# synthbadge.net
KiCad netlist of a schematic drawn in EAGLE
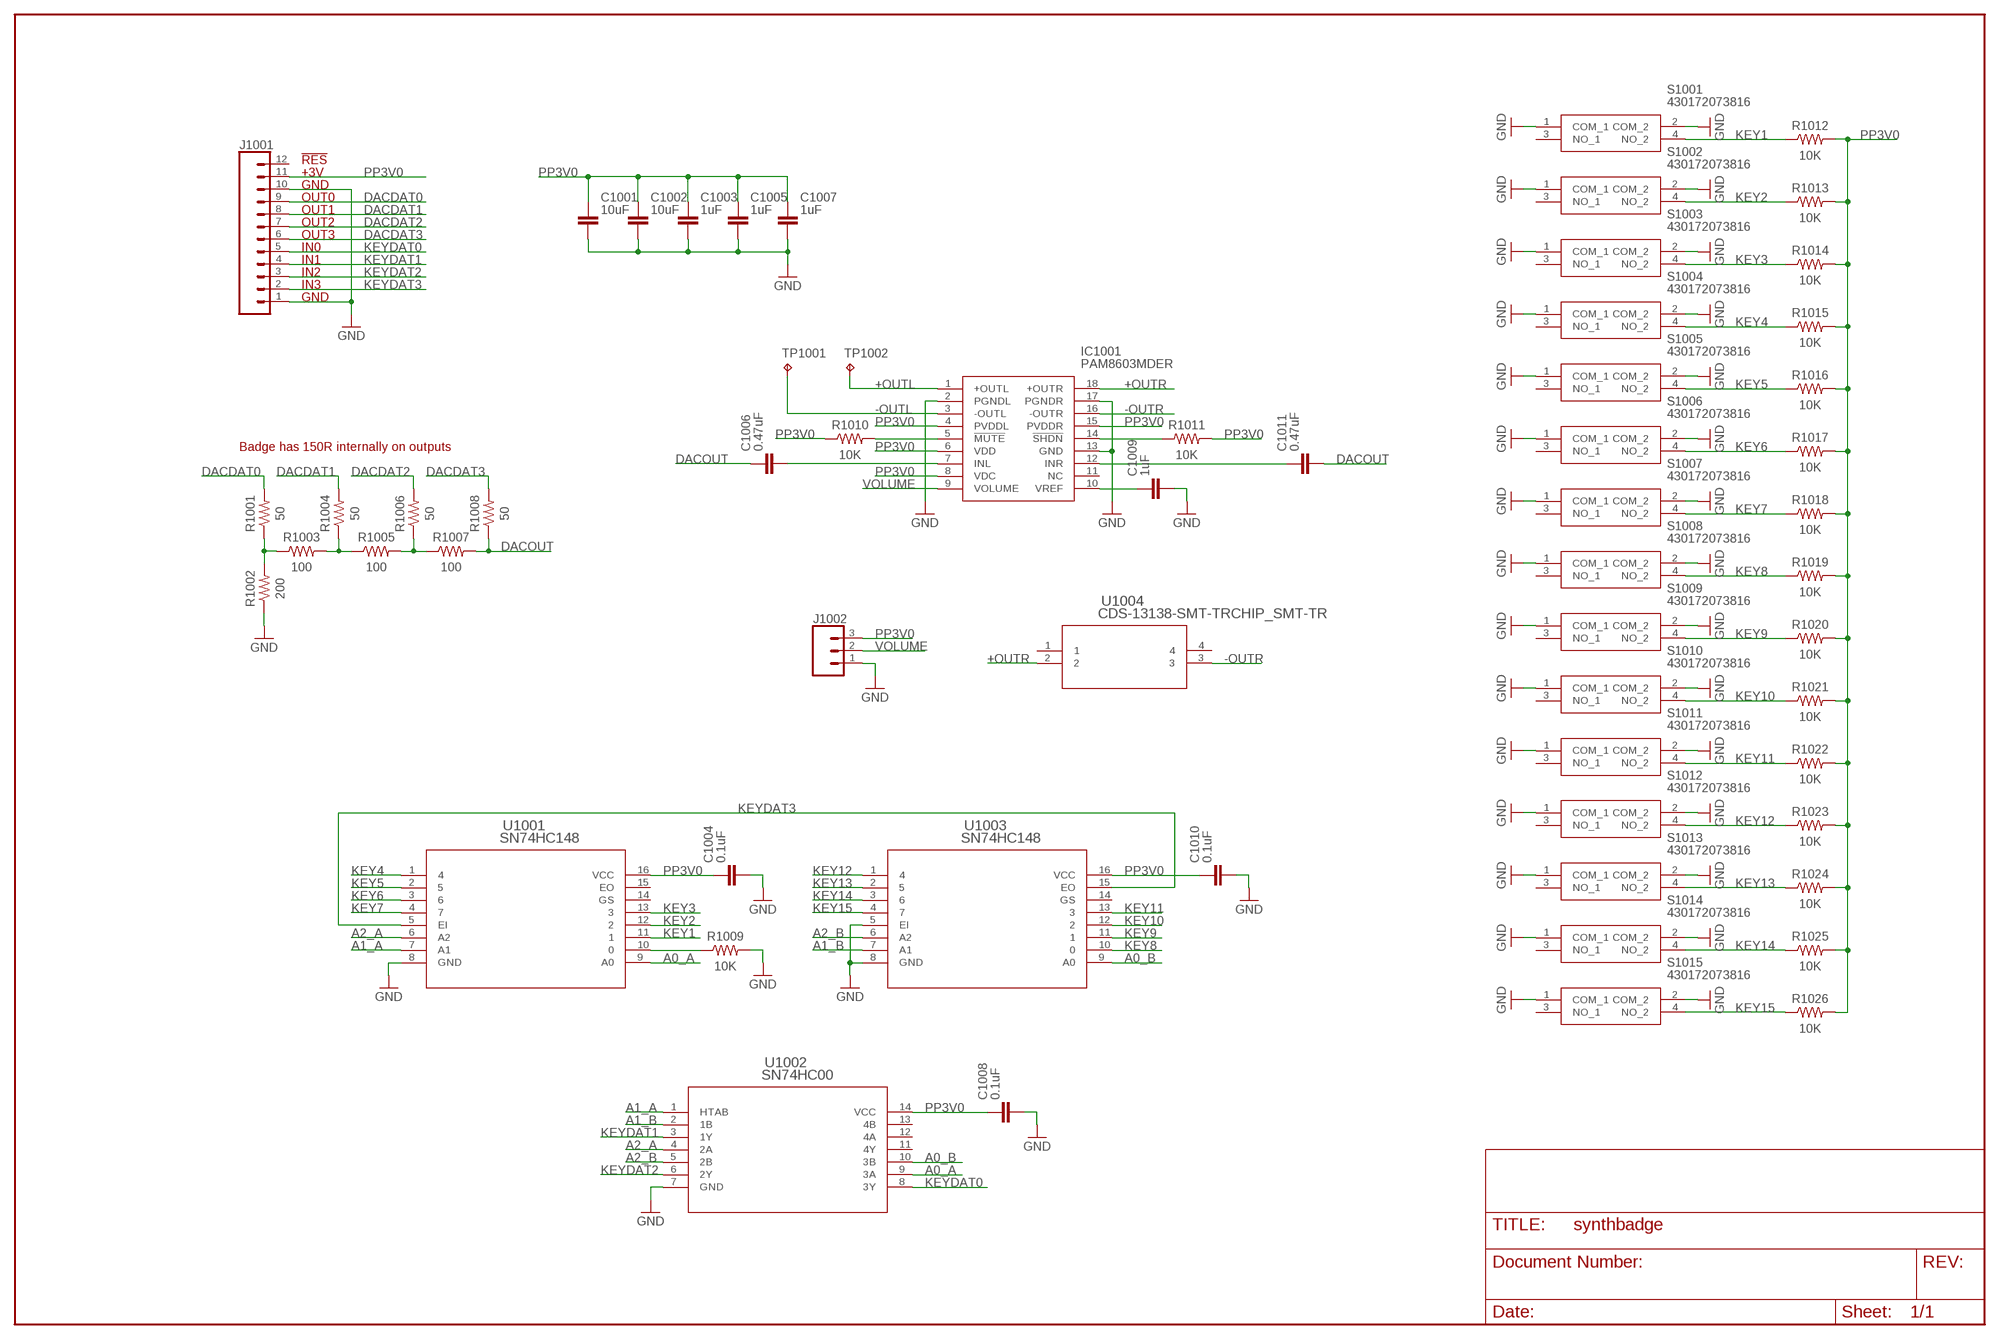
[diagram p0: schematic, sheet 1]

(export (version "E")
  (design (tool "Eeschema 10.0.6"))
  (components
    (comp (ref "C1001")
      (value "10uF")
      (footprint "eagle-import:CAPC2012X110")
      (libsource (lib "eagle-import") (part "CCHIP-0805(2012-METRIC)_"))
    )
    (comp (ref "C1002")
      (value "10uF")
      (footprint "eagle-import:CAPC2012X110")
      (libsource (lib "eagle-import") (part "CCHIP-0805(2012-METRIC)_"))
    )
    (comp (ref "C1003")
      (value "1uF")
      (footprint "eagle-import:CAPC2012X110")
      (libsource (lib "eagle-import") (part "CCHIP-0805(2012-METRIC)_"))
    )
    (comp (ref "C1004")
      (value "0.1uF")
      (footprint "eagle-import:CAPC2012X110")
      (libsource (lib "eagle-import") (part "CCHIP-0805(2012-METRIC)_"))
    )
    (comp (ref "C1005")
      (value "1uF")
      (footprint "eagle-import:CAPC2012X110")
      (libsource (lib "eagle-import") (part "CCHIP-0805(2012-METRIC)_"))
    )
    (comp (ref "C1006")
      (value "0.47uF")
      (footprint "eagle-import:CAPC2012X110")
      (libsource (lib "eagle-import") (part "CCHIP-0805(2012-METRIC)_"))
    )
    (comp (ref "C1007")
      (value "1uF")
      (footprint "eagle-import:CAPC2012X110")
      (libsource (lib "eagle-import") (part "CCHIP-0805(2012-METRIC)_"))
    )
    (comp (ref "C1008")
      (value "0.1uF")
      (footprint "eagle-import:CAPC2012X110")
      (libsource (lib "eagle-import") (part "CCHIP-0805(2012-METRIC)_"))
    )
    (comp (ref "C1009")
      (value "1uF")
      (footprint "eagle-import:CAPC2012X110")
      (libsource (lib "eagle-import") (part "CCHIP-0805(2012-METRIC)_"))
    )
    (comp (ref "C1010")
      (value "0.1uF")
      (footprint "eagle-import:CAPC2012X110")
      (libsource (lib "eagle-import") (part "CCHIP-0805(2012-METRIC)_"))
    )
    (comp (ref "C1011")
      (value "0.47uF")
      (footprint "eagle-import:CAPC2012X110")
      (libsource (lib "eagle-import") (part "CCHIP-0805(2012-METRIC)_"))
    )
    (comp (ref "IC1001")
      (value "PAM8603MDER")
      (footprint "eagle-import:SOIC127P1032X270-18N")
      (fields (field (name "MOUSER_PART_NUMBER") "621-PAM8603MDER"))
      (libsource (lib "eagle-import") (part "PAM8603MDER"))
    )
    (comp (ref "J1001")
      (value "CONN_12")
      (footprint "eagle-import:1X12")
      (libsource (lib "eagle-import") (part "CONN_12"))
    )
    (comp (ref "J1002")
      (value "CONN_03")
      (footprint "eagle-import:1X03")
      (libsource (lib "eagle-import") (part "CONN_03"))
    )
    (comp (ref "R1001")
      (value "50")
      (footprint "eagle-import:RESC2012X65")
      (libsource (lib "eagle-import") (part "R-USCHIP-0805(2012-METRIC)_"))
    )
    (comp (ref "R1002")
      (value "200")
      (footprint "eagle-import:RESC2012X65")
      (libsource (lib "eagle-import") (part "R-USCHIP-0805(2012-METRIC)_"))
    )
    (comp (ref "R1003")
      (value "100")
      (footprint "eagle-import:RESC2012X65")
      (libsource (lib "eagle-import") (part "R-USCHIP-0805(2012-METRIC)_"))
    )
    (comp (ref "R1004")
      (value "50")
      (footprint "eagle-import:RESC2012X65")
      (libsource (lib "eagle-import") (part "R-USCHIP-0805(2012-METRIC)_"))
    )
    (comp (ref "R1005")
      (value "100")
      (footprint "eagle-import:RESC2012X65")
      (libsource (lib "eagle-import") (part "R-USCHIP-0805(2012-METRIC)_"))
    )
    (comp (ref "R1006")
      (value "50")
      (footprint "eagle-import:RESC2012X65")
      (libsource (lib "eagle-import") (part "R-USCHIP-0805(2012-METRIC)_"))
    )
    (comp (ref "R1007")
      (value "100")
      (footprint "eagle-import:RESC2012X65")
      (libsource (lib "eagle-import") (part "R-USCHIP-0805(2012-METRIC)_"))
    )
    (comp (ref "R1008")
      (value "50")
      (footprint "eagle-import:RESC2012X65")
      (libsource (lib "eagle-import") (part "R-USCHIP-0805(2012-METRIC)_"))
    )
    (comp (ref "R1009")
      (value "10K")
      (footprint "eagle-import:RESC2012X65")
      (libsource (lib "eagle-import") (part "R-USCHIP-0805(2012-METRIC)_"))
    )
    (comp (ref "R1010")
      (value "10K")
      (footprint "eagle-import:RESC2012X65")
      (libsource (lib "eagle-import") (part "R-USCHIP-0805(2012-METRIC)_"))
    )
    (comp (ref "R1011")
      (value "10K")
      (footprint "eagle-import:RESC2012X65")
      (libsource (lib "eagle-import") (part "R-USCHIP-0805(2012-METRIC)_"))
    )
    (comp (ref "R1012")
      (value "10K")
      (footprint "eagle-import:RESC2012X65")
      (libsource (lib "eagle-import") (part "R-USCHIP-0805(2012-METRIC)_"))
    )
    (comp (ref "R1013")
      (value "10K")
      (footprint "eagle-import:RESC2012X65")
      (libsource (lib "eagle-import") (part "R-USCHIP-0805(2012-METRIC)_"))
    )
    (comp (ref "R1014")
      (value "10K")
      (footprint "eagle-import:RESC2012X65")
      (libsource (lib "eagle-import") (part "R-USCHIP-0805(2012-METRIC)_"))
    )
    (comp (ref "R1015")
      (value "10K")
      (footprint "eagle-import:RESC2012X65")
      (libsource (lib "eagle-import") (part "R-USCHIP-0805(2012-METRIC)_"))
    )
    (comp (ref "R1016")
      (value "10K")
      (footprint "eagle-import:RESC2012X65")
      (libsource (lib "eagle-import") (part "R-USCHIP-0805(2012-METRIC)_"))
    )
    (comp (ref "R1017")
      (value "10K")
      (footprint "eagle-import:RESC2012X65")
      (libsource (lib "eagle-import") (part "R-USCHIP-0805(2012-METRIC)_"))
    )
    (comp (ref "R1018")
      (value "10K")
      (footprint "eagle-import:RESC2012X65")
      (libsource (lib "eagle-import") (part "R-USCHIP-0805(2012-METRIC)_"))
    )
    (comp (ref "R1019")
      (value "10K")
      (footprint "eagle-import:RESC2012X65")
      (libsource (lib "eagle-import") (part "R-USCHIP-0805(2012-METRIC)_"))
    )
    (comp (ref "R1020")
      (value "10K")
      (footprint "eagle-import:RESC2012X65")
      (libsource (lib "eagle-import") (part "R-USCHIP-0805(2012-METRIC)_"))
    )
    (comp (ref "R1021")
      (value "10K")
      (footprint "eagle-import:RESC2012X65")
      (libsource (lib "eagle-import") (part "R-USCHIP-0805(2012-METRIC)_"))
    )
    (comp (ref "R1022")
      (value "10K")
      (footprint "eagle-import:RESC2012X65")
      (libsource (lib "eagle-import") (part "R-USCHIP-0805(2012-METRIC)_"))
    )
    (comp (ref "R1023")
      (value "10K")
      (footprint "eagle-import:RESC2012X65")
      (libsource (lib "eagle-import") (part "R-USCHIP-0805(2012-METRIC)_"))
    )
    (comp (ref "R1024")
      (value "10K")
      (footprint "eagle-import:RESC2012X65")
      (libsource (lib "eagle-import") (part "R-USCHIP-0805(2012-METRIC)_"))
    )
    (comp (ref "R1025")
      (value "10K")
      (footprint "eagle-import:RESC2012X65")
      (libsource (lib "eagle-import") (part "R-USCHIP-0805(2012-METRIC)_"))
    )
    (comp (ref "R1026")
      (value "10K")
      (footprint "eagle-import:RESC2012X65")
      (libsource (lib "eagle-import") (part "R-USCHIP-0805(2012-METRIC)_"))
    )
    (comp (ref "S1001")
      (value "430172073816")
      (footprint "eagle-import:430172073816")
      (fields (field (name "MOUSER_PART_NUMBER") "710-430172073816"))
      (libsource (lib "eagle-import") (part "430172073816"))
    )
    (comp (ref "S1002")
      (value "430172073816")
      (footprint "eagle-import:430172073816")
      (fields (field (name "MOUSER_PART_NUMBER") "710-430172073816"))
      (libsource (lib "eagle-import") (part "430172073816"))
    )
    (comp (ref "S1003")
      (value "430172073816")
      (footprint "eagle-import:430172073816")
      (fields (field (name "MOUSER_PART_NUMBER") "710-430172073816"))
      (libsource (lib "eagle-import") (part "430172073816"))
    )
    (comp (ref "S1004")
      (value "430172073816")
      (footprint "eagle-import:430172073816")
      (fields (field (name "MOUSER_PART_NUMBER") "710-430172073816"))
      (libsource (lib "eagle-import") (part "430172073816"))
    )
    (comp (ref "S1005")
      (value "430172073816")
      (footprint "eagle-import:430172073816")
      (fields (field (name "MOUSER_PART_NUMBER") "710-430172073816"))
      (libsource (lib "eagle-import") (part "430172073816"))
    )
    (comp (ref "S1006")
      (value "430172073816")
      (footprint "eagle-import:430172073816")
      (fields (field (name "MOUSER_PART_NUMBER") "710-430172073816"))
      (libsource (lib "eagle-import") (part "430172073816"))
    )
    (comp (ref "S1007")
      (value "430172073816")
      (footprint "eagle-import:430172073816")
      (fields (field (name "MOUSER_PART_NUMBER") "710-430172073816"))
      (libsource (lib "eagle-import") (part "430172073816"))
    )
    (comp (ref "S1008")
      (value "430172073816")
      (footprint "eagle-import:430172073816")
      (fields (field (name "MOUSER_PART_NUMBER") "710-430172073816"))
      (libsource (lib "eagle-import") (part "430172073816"))
    )
    (comp (ref "S1009")
      (value "430172073816")
      (footprint "eagle-import:430172073816")
      (fields (field (name "MOUSER_PART_NUMBER") "710-430172073816"))
      (libsource (lib "eagle-import") (part "430172073816"))
    )
    (comp (ref "S1010")
      (value "430172073816")
      (footprint "eagle-import:430172073816")
      (fields (field (name "MOUSER_PART_NUMBER") "710-430172073816"))
      (libsource (lib "eagle-import") (part "430172073816"))
    )
    (comp (ref "S1011")
      (value "430172073816")
      (footprint "eagle-import:430172073816")
      (fields (field (name "MOUSER_PART_NUMBER") "710-430172073816"))
      (libsource (lib "eagle-import") (part "430172073816"))
    )
    (comp (ref "S1012")
      (value "430172073816")
      (footprint "eagle-import:430172073816")
      (fields (field (name "MOUSER_PART_NUMBER") "710-430172073816"))
      (libsource (lib "eagle-import") (part "430172073816"))
    )
    (comp (ref "S1013")
      (value "430172073816")
      (footprint "eagle-import:430172073816")
      (fields (field (name "MOUSER_PART_NUMBER") "710-430172073816"))
      (libsource (lib "eagle-import") (part "430172073816"))
    )
    (comp (ref "S1014")
      (value "430172073816")
      (footprint "eagle-import:430172073816")
      (fields (field (name "MOUSER_PART_NUMBER") "710-430172073816"))
      (libsource (lib "eagle-import") (part "430172073816"))
    )
    (comp (ref "S1015")
      (value "430172073816")
      (footprint "eagle-import:430172073816")
      (fields (field (name "MOUSER_PART_NUMBER") "710-430172073816"))
      (libsource (lib "eagle-import") (part "430172073816"))
    )
    (comp (ref "TP1001")
      (value "TPB2,54")
      (footprint "eagle-import:B2,54")
      (libsource (lib "eagle-import") (part "TPB2,54"))
    )
    (comp (ref "TP1002")
      (value "TPB2,54")
      (footprint "eagle-import:B2,54")
      (libsource (lib "eagle-import") (part "TPB2,54"))
    )
    (comp (ref "U1001")
      (value "SN74HC148")
      (footprint "eagle-import:D16_TEX")
      (fields
        (field (name "MANUFACTURER_PART_NUMBER") "SN74HC148_D_16")
        (field (name "COPYRIGHT") "Copyright (C) 2022 Ultra Librarian. All rights reserved.")
      )
      (libsource (lib "eagle-import") (part "SN74HC148_D_16D16_TEX"))
    )
    (comp (ref "U1002")
      (value "SN74HC00")
      (footprint "eagle-import:D14_TEX")
      (fields
        (field (name "MANUFACTURER_PART_NUMBER") "SN74HC00_D_14")
        (field (name "COPYRIGHT") "Copyright (C) 2022 Ultra Librarian. All rights reserved.")
      )
      (libsource (lib "eagle-import") (part "SN74HC00_D_14D14_TEX"))
    )
    (comp (ref "U1003")
      (value "SN74HC148")
      (footprint "eagle-import:D16_TEX")
      (fields
        (field (name "MANUFACTURER_PART_NUMBER") "SN74HC148_D_16")
        (field (name "COPYRIGHT") "Copyright (C) 2022 Ultra Librarian. All rights reserved.")
      )
      (libsource (lib "eagle-import") (part "SN74HC148_D_16D16_TEX"))
    )
    (comp (ref "U1004")
      (value "CDS-13138-SMT-TRCHIP_SMT-TR")
      (footprint "eagle-import:CHIP_SMT-TR")
      (fields
        (field (name "MANUFACTURER_PART_NUMBER") "CDS-13138-SMT-TR")
        (field (name "COPYRIGHT") "Copyright (C) 2022 Ultra Librarian. All rights reserved.")
      )
      (libsource (lib "eagle-import") (part "CDS-13138-SMT-TRCHIP_SMT-TR"))
    )
  )
  (nets
    (net (code "1") (name "/+OUTL") (class "Default")
      (node (ref "IC1001") (pin "1") (pinfunction "+OUTL_1") (pintype "bidirectional"))
      (node (ref "TP1002") (pin "TP") (pinfunction "TP_TP") (pintype "input"))
    )
    (net (code "2") (name "/+OUTR") (class "Default")
      (node (ref "IC1001") (pin "18") (pinfunction "+OUTR_18") (pintype "bidirectional"))
      (node (ref "U1004") (pin "2") (pinfunction "2_2") (pintype "passive"))
    )
    (net (code "3") (name "/-OUTL") (class "Default")
      (node (ref "IC1001") (pin "3") (pinfunction "-OUTL_3") (pintype "bidirectional"))
      (node (ref "TP1001") (pin "TP") (pinfunction "TP_TP") (pintype "input"))
    )
    (net (code "4") (name "/-OUTR") (class "Default")
      (node (ref "IC1001") (pin "16") (pinfunction "-OUTR_16") (pintype "bidirectional"))
      (node (ref "U1004") (pin "3") (pinfunction "3_3") (pintype "passive"))
    )
    (net (code "5") (name "/A0_A") (class "Default")
      (node (ref "U1001") (pin "9") (pinfunction "A0_9") (pintype "output"))
      (node (ref "U1002") (pin "9") (pinfunction "3A_9") (pintype "input"))
    )
    (net (code "6") (name "/A0_B") (class "Default")
      (node (ref "U1002") (pin "10") (pinfunction "3B_10") (pintype "input"))
      (node (ref "U1003") (pin "9") (pinfunction "A0_9") (pintype "output"))
    )
    (net (code "7") (name "/A1_A") (class "Default")
      (node (ref "U1001") (pin "7") (pinfunction "A1_7") (pintype "output"))
      (node (ref "U1002") (pin "1") (pinfunction "HTAB_1") (pintype "power_in"))
    )
    (net (code "8") (name "/A1_B") (class "Default")
      (node (ref "U1002") (pin "2") (pinfunction "1B_2") (pintype "input"))
      (node (ref "U1003") (pin "7") (pinfunction "A1_7") (pintype "output"))
    )
    (net (code "9") (name "/A2_A") (class "Default")
      (node (ref "U1001") (pin "6") (pinfunction "A2_6") (pintype "output"))
      (node (ref "U1002") (pin "4") (pinfunction "2A_4") (pintype "input"))
    )
    (net (code "10") (name "/A2_B") (class "Default")
      (node (ref "U1002") (pin "5") (pinfunction "2B_5") (pintype "input"))
      (node (ref "U1003") (pin "6") (pinfunction "A2_6") (pintype "output"))
    )
    (net (code "11") (name "/DACDAT0") (class "Default")
      (node (ref "J1001") (pin "9") (pinfunction "9_9") (pintype "passive"))
      (node (ref "R1001") (pin "2") (pinfunction "2_2") (pintype "passive"))
    )
    (net (code "12") (name "/DACDAT1") (class "Default")
      (node (ref "J1001") (pin "8") (pinfunction "8_8") (pintype "passive"))
      (node (ref "R1004") (pin "2") (pinfunction "2_2") (pintype "passive"))
    )
    (net (code "13") (name "/DACDAT2") (class "Default")
      (node (ref "J1001") (pin "7") (pinfunction "7_7") (pintype "passive"))
      (node (ref "R1006") (pin "2") (pinfunction "2_2") (pintype "passive"))
    )
    (net (code "14") (name "/DACDAT3") (class "Default")
      (node (ref "J1001") (pin "6") (pinfunction "6_6") (pintype "passive"))
      (node (ref "R1008") (pin "2") (pinfunction "2_2") (pintype "passive"))
    )
    (net (code "15") (name "/DACOUT") (class "Default")
      (node (ref "C1006") (pin "1") (pinfunction "1_1") (pintype "passive"))
      (node (ref "C1011") (pin "2") (pinfunction "2_2") (pintype "passive"))
      (node (ref "R1007") (pin "2") (pinfunction "2_2") (pintype "passive"))
      (node (ref "R1008") (pin "1") (pinfunction "1_1") (pintype "passive"))
    )
    (net (code "16") (name "/KEY1") (class "Default")
      (node (ref "R1012") (pin "1") (pinfunction "1_1") (pintype "passive"))
      (node (ref "S1001") (pin "4") (pinfunction "NO_2_4") (pintype "bidirectional"))
      (node (ref "U1001") (pin "11") (pinfunction "1_11") (pintype "input"))
    )
    (net (code "17") (name "/KEY2") (class "Default")
      (node (ref "R1013") (pin "1") (pinfunction "1_1") (pintype "passive"))
      (node (ref "S1002") (pin "4") (pinfunction "NO_2_4") (pintype "bidirectional"))
      (node (ref "U1001") (pin "12") (pinfunction "2_12") (pintype "input"))
    )
    (net (code "18") (name "/KEY3") (class "Default")
      (node (ref "R1014") (pin "1") (pinfunction "1_1") (pintype "passive"))
      (node (ref "S1003") (pin "4") (pinfunction "NO_2_4") (pintype "bidirectional"))
      (node (ref "U1001") (pin "13") (pinfunction "3_13") (pintype "input"))
    )
    (net (code "19") (name "/KEY4") (class "Default")
      (node (ref "R1015") (pin "1") (pinfunction "1_1") (pintype "passive"))
      (node (ref "S1004") (pin "4") (pinfunction "NO_2_4") (pintype "bidirectional"))
      (node (ref "U1001") (pin "1") (pinfunction "4_1") (pintype "input"))
    )
    (net (code "20") (name "/KEY5") (class "Default")
      (node (ref "R1016") (pin "1") (pinfunction "1_1") (pintype "passive"))
      (node (ref "S1005") (pin "4") (pinfunction "NO_2_4") (pintype "bidirectional"))
      (node (ref "U1001") (pin "2") (pinfunction "5_2") (pintype "input"))
    )
    (net (code "21") (name "/KEY6") (class "Default")
      (node (ref "R1017") (pin "1") (pinfunction "1_1") (pintype "passive"))
      (node (ref "S1006") (pin "4") (pinfunction "NO_2_4") (pintype "bidirectional"))
      (node (ref "U1001") (pin "3") (pinfunction "6_3") (pintype "input"))
    )
    (net (code "22") (name "/KEY7") (class "Default")
      (node (ref "R1018") (pin "1") (pinfunction "1_1") (pintype "passive"))
      (node (ref "S1007") (pin "4") (pinfunction "NO_2_4") (pintype "bidirectional"))
      (node (ref "U1001") (pin "4") (pinfunction "7_4") (pintype "input"))
    )
    (net (code "23") (name "/KEY8") (class "Default")
      (node (ref "R1019") (pin "1") (pinfunction "1_1") (pintype "passive"))
      (node (ref "S1008") (pin "4") (pinfunction "NO_2_4") (pintype "bidirectional"))
      (node (ref "U1003") (pin "10") (pinfunction "0_10") (pintype "input"))
    )
    (net (code "24") (name "/KEY9") (class "Default")
      (node (ref "R1020") (pin "1") (pinfunction "1_1") (pintype "passive"))
      (node (ref "S1009") (pin "4") (pinfunction "NO_2_4") (pintype "bidirectional"))
      (node (ref "U1003") (pin "11") (pinfunction "1_11") (pintype "input"))
    )
    (net (code "25") (name "/KEY10") (class "Default")
      (node (ref "R1021") (pin "1") (pinfunction "1_1") (pintype "passive"))
      (node (ref "S1010") (pin "4") (pinfunction "NO_2_4") (pintype "bidirectional"))
      (node (ref "U1003") (pin "12") (pinfunction "2_12") (pintype "input"))
    )
    (net (code "26") (name "/KEY11") (class "Default")
      (node (ref "R1022") (pin "1") (pinfunction "1_1") (pintype "passive"))
      (node (ref "S1011") (pin "4") (pinfunction "NO_2_4") (pintype "bidirectional"))
      (node (ref "U1003") (pin "13") (pinfunction "3_13") (pintype "input"))
    )
    (net (code "27") (name "/KEY12") (class "Default")
      (node (ref "R1023") (pin "1") (pinfunction "1_1") (pintype "passive"))
      (node (ref "S1012") (pin "4") (pinfunction "NO_2_4") (pintype "bidirectional"))
      (node (ref "U1003") (pin "1") (pinfunction "4_1") (pintype "input"))
    )
    (net (code "28") (name "/KEY13") (class "Default")
      (node (ref "R1024") (pin "1") (pinfunction "1_1") (pintype "passive"))
      (node (ref "S1013") (pin "4") (pinfunction "NO_2_4") (pintype "bidirectional"))
      (node (ref "U1003") (pin "2") (pinfunction "5_2") (pintype "input"))
    )
    (net (code "29") (name "/KEY14") (class "Default")
      (node (ref "R1025") (pin "1") (pinfunction "1_1") (pintype "passive"))
      (node (ref "S1014") (pin "4") (pinfunction "NO_2_4") (pintype "bidirectional"))
      (node (ref "U1003") (pin "3") (pinfunction "6_3") (pintype "input"))
    )
    (net (code "30") (name "/KEY15") (class "Default")
      (node (ref "R1026") (pin "1") (pinfunction "1_1") (pintype "passive"))
      (node (ref "S1015") (pin "4") (pinfunction "NO_2_4") (pintype "bidirectional"))
      (node (ref "U1003") (pin "4") (pinfunction "7_4") (pintype "input"))
    )
    (net (code "31") (name "/KEYDAT0") (class "Default")
      (node (ref "J1001") (pin "5") (pinfunction "5_5") (pintype "passive"))
      (node (ref "U1002") (pin "8") (pinfunction "3Y_8") (pintype "output"))
    )
    (net (code "32") (name "/KEYDAT1") (class "Default")
      (node (ref "J1001") (pin "4") (pinfunction "4_4") (pintype "passive"))
      (node (ref "U1002") (pin "3") (pinfunction "1Y_3") (pintype "output"))
    )
    (net (code "33") (name "/KEYDAT2") (class "Default")
      (node (ref "J1001") (pin "3") (pinfunction "3_3") (pintype "passive"))
      (node (ref "U1002") (pin "6") (pinfunction "2Y_6") (pintype "output"))
    )
    (net (code "34") (name "/KEYDAT3") (class "Default")
      (node (ref "J1001") (pin "2") (pinfunction "2_2") (pintype "passive"))
      (node (ref "U1001") (pin "5") (pinfunction "EI_5") (pintype "input"))
      (node (ref "U1003") (pin "15") (pinfunction "EO_15") (pintype "output"))
    )
    (net (code "35") (name "/PP3V0") (class "Default")
      (node (ref "C1001") (pin "1") (pinfunction "1_1") (pintype "passive"))
      (node (ref "C1002") (pin "1") (pinfunction "1_1") (pintype "passive"))
      (node (ref "C1003") (pin "1") (pinfunction "1_1") (pintype "passive"))
      (node (ref "C1004") (pin "1") (pinfunction "1_1") (pintype "passive"))
      (node (ref "C1005") (pin "1") (pinfunction "1_1") (pintype "passive"))
      (node (ref "C1007") (pin "1") (pinfunction "1_1") (pintype "passive"))
      (node (ref "C1008") (pin "1") (pinfunction "1_1") (pintype "passive"))
      (node (ref "C1010") (pin "1") (pinfunction "1_1") (pintype "passive"))
      (node (ref "IC1001") (pin "15") (pinfunction "PVDDR_15") (pintype "bidirectional"))
      (node (ref "IC1001") (pin "4") (pinfunction "PVDDL_4") (pintype "bidirectional"))
      (node (ref "IC1001") (pin "6") (pinfunction "VDD_6") (pintype "bidirectional"))
      (node (ref "IC1001") (pin "8") (pinfunction "VDC_8") (pintype "bidirectional"))
      (node (ref "J1001") (pin "11") (pinfunction "11_11") (pintype "passive"))
      (node (ref "J1002") (pin "3") (pinfunction "3_3") (pintype "passive"))
      (node (ref "R1010") (pin "1") (pinfunction "1_1") (pintype "passive"))
      (node (ref "R1011") (pin "2") (pinfunction "2_2") (pintype "passive"))
      (node (ref "R1012") (pin "2") (pinfunction "2_2") (pintype "passive"))
      (node (ref "R1013") (pin "2") (pinfunction "2_2") (pintype "passive"))
      (node (ref "R1014") (pin "2") (pinfunction "2_2") (pintype "passive"))
      (node (ref "R1015") (pin "2") (pinfunction "2_2") (pintype "passive"))
      (node (ref "R1016") (pin "2") (pinfunction "2_2") (pintype "passive"))
      (node (ref "R1017") (pin "2") (pinfunction "2_2") (pintype "passive"))
      (node (ref "R1018") (pin "2") (pinfunction "2_2") (pintype "passive"))
      (node (ref "R1019") (pin "2") (pinfunction "2_2") (pintype "passive"))
      (node (ref "R1020") (pin "2") (pinfunction "2_2") (pintype "passive"))
      (node (ref "R1021") (pin "2") (pinfunction "2_2") (pintype "passive"))
      (node (ref "R1022") (pin "2") (pinfunction "2_2") (pintype "passive"))
      (node (ref "R1023") (pin "2") (pinfunction "2_2") (pintype "passive"))
      (node (ref "R1024") (pin "2") (pinfunction "2_2") (pintype "passive"))
      (node (ref "R1025") (pin "2") (pinfunction "2_2") (pintype "passive"))
      (node (ref "R1026") (pin "2") (pinfunction "2_2") (pintype "passive"))
      (node (ref "U1001") (pin "16") (pinfunction "VCC_16") (pintype "power_in"))
      (node (ref "U1002") (pin "14") (pinfunction "VCC_14") (pintype "power_in"))
      (node (ref "U1003") (pin "16") (pinfunction "VCC_16") (pintype "power_in"))
    )
    (net (code "36") (name "/VOLUME") (class "Default")
      (node (ref "IC1001") (pin "9") (pinfunction "VOLUME_9") (pintype "bidirectional"))
      (node (ref "J1002") (pin "2") (pinfunction "2_2") (pintype "passive"))
    )
    (net (code "37") (name "GND") (class "Default")
      (node (ref "C1001") (pin "2") (pinfunction "2_2") (pintype "passive"))
      (node (ref "C1002") (pin "2") (pinfunction "2_2") (pintype "passive"))
      (node (ref "C1003") (pin "2") (pinfunction "2_2") (pintype "passive"))
      (node (ref "C1004") (pin "2") (pinfunction "2_2") (pintype "passive"))
      (node (ref "C1005") (pin "2") (pinfunction "2_2") (pintype "passive"))
      (node (ref "C1007") (pin "2") (pinfunction "2_2") (pintype "passive"))
      (node (ref "C1008") (pin "2") (pinfunction "2_2") (pintype "passive"))
      (node (ref "C1009") (pin "2") (pinfunction "2_2") (pintype "passive"))
      (node (ref "C1010") (pin "2") (pinfunction "2_2") (pintype "passive"))
      (node (ref "IC1001") (pin "13") (pinfunction "GND_13") (pintype "bidirectional"))
      (node (ref "IC1001") (pin "17") (pinfunction "PGNDR_17") (pintype "bidirectional"))
      (node (ref "IC1001") (pin "2") (pinfunction "PGNDL_2") (pintype "bidirectional"))
      (node (ref "J1001") (pin "1") (pinfunction "1_1") (pintype "passive"))
      (node (ref "J1001") (pin "10") (pinfunction "10_10") (pintype "passive"))
      (node (ref "J1002") (pin "1") (pinfunction "1_1") (pintype "passive"))
      (node (ref "R1002") (pin "1") (pinfunction "1_1") (pintype "passive"))
      (node (ref "R1009") (pin "2") (pinfunction "2_2") (pintype "passive"))
      (node (ref "S1001") (pin "1") (pinfunction "COM_1_1") (pintype "bidirectional"))
      (node (ref "S1001") (pin "2") (pinfunction "COM_2_2") (pintype "bidirectional"))
      (node (ref "S1002") (pin "1") (pinfunction "COM_1_1") (pintype "bidirectional"))
      (node (ref "S1002") (pin "2") (pinfunction "COM_2_2") (pintype "bidirectional"))
      (node (ref "S1003") (pin "1") (pinfunction "COM_1_1") (pintype "bidirectional"))
      (node (ref "S1003") (pin "2") (pinfunction "COM_2_2") (pintype "bidirectional"))
      (node (ref "S1004") (pin "1") (pinfunction "COM_1_1") (pintype "bidirectional"))
      (node (ref "S1004") (pin "2") (pinfunction "COM_2_2") (pintype "bidirectional"))
      (node (ref "S1005") (pin "1") (pinfunction "COM_1_1") (pintype "bidirectional"))
      (node (ref "S1005") (pin "2") (pinfunction "COM_2_2") (pintype "bidirectional"))
      (node (ref "S1006") (pin "1") (pinfunction "COM_1_1") (pintype "bidirectional"))
      (node (ref "S1006") (pin "2") (pinfunction "COM_2_2") (pintype "bidirectional"))
      (node (ref "S1007") (pin "1") (pinfunction "COM_1_1") (pintype "bidirectional"))
      (node (ref "S1007") (pin "2") (pinfunction "COM_2_2") (pintype "bidirectional"))
      (node (ref "S1008") (pin "1") (pinfunction "COM_1_1") (pintype "bidirectional"))
      (node (ref "S1008") (pin "2") (pinfunction "COM_2_2") (pintype "bidirectional"))
      (node (ref "S1009") (pin "1") (pinfunction "COM_1_1") (pintype "bidirectional"))
      (node (ref "S1009") (pin "2") (pinfunction "COM_2_2") (pintype "bidirectional"))
      (node (ref "S1010") (pin "1") (pinfunction "COM_1_1") (pintype "bidirectional"))
      (node (ref "S1010") (pin "2") (pinfunction "COM_2_2") (pintype "bidirectional"))
      (node (ref "S1011") (pin "1") (pinfunction "COM_1_1") (pintype "bidirectional"))
      (node (ref "S1011") (pin "2") (pinfunction "COM_2_2") (pintype "bidirectional"))
      (node (ref "S1012") (pin "1") (pinfunction "COM_1_1") (pintype "bidirectional"))
      (node (ref "S1012") (pin "2") (pinfunction "COM_2_2") (pintype "bidirectional"))
      (node (ref "S1013") (pin "1") (pinfunction "COM_1_1") (pintype "bidirectional"))
      (node (ref "S1013") (pin "2") (pinfunction "COM_2_2") (pintype "bidirectional"))
      (node (ref "S1014") (pin "1") (pinfunction "COM_1_1") (pintype "bidirectional"))
      (node (ref "S1014") (pin "2") (pinfunction "COM_2_2") (pintype "bidirectional"))
      (node (ref "S1015") (pin "1") (pinfunction "COM_1_1") (pintype "bidirectional"))
      (node (ref "S1015") (pin "2") (pinfunction "COM_2_2") (pintype "bidirectional"))
      (node (ref "U1001") (pin "8") (pinfunction "GND_8") (pintype "power_in"))
      (node (ref "U1002") (pin "7") (pinfunction "GND_7") (pintype "power_in"))
      (node (ref "U1003") (pin "5") (pinfunction "EI_5") (pintype "input"))
      (node (ref "U1003") (pin "8") (pinfunction "GND_8") (pintype "power_in"))
    )
    (net (code "38") (name "Net-(IC1001-INL)") (class "Default")
      (node (ref "C1006") (pin "2") (pinfunction "2_2") (pintype "passive"))
      (node (ref "IC1001") (pin "7") (pinfunction "INL_7") (pintype "bidirectional"))
    )
    (net (code "39") (name "Net-(IC1001-INR)") (class "Default")
      (node (ref "C1011") (pin "1") (pinfunction "1_1") (pintype "passive"))
      (node (ref "IC1001") (pin "12") (pinfunction "INR_12") (pintype "bidirectional"))
    )
    (net (code "40") (name "Net-(IC1001-VREF)") (class "Default")
      (node (ref "C1009") (pin "1") (pinfunction "1_1") (pintype "passive"))
      (node (ref "IC1001") (pin "10") (pinfunction "VREF_10") (pintype "bidirectional"))
    )
    (net (code "41") (name "Net-(IC1001-~{MUTE})") (class "Default")
      (node (ref "IC1001") (pin "5") (pinfunction "~{MUTE}_5") (pintype "bidirectional"))
      (node (ref "R1010") (pin "2") (pinfunction "2_2") (pintype "passive"))
    )
    (net (code "42") (name "Net-(IC1001-~{SHDN})") (class "Default")
      (node (ref "IC1001") (pin "14") (pinfunction "~{SHDN}_14") (pintype "bidirectional"))
      (node (ref "R1011") (pin "1") (pinfunction "1_1") (pintype "passive"))
    )
    (net (code "43") (name "Net-(R1001-Pad1)") (class "Default")
      (node (ref "R1001") (pin "1") (pinfunction "1_1") (pintype "passive"))
      (node (ref "R1002") (pin "2") (pinfunction "2_2") (pintype "passive"))
      (node (ref "R1003") (pin "1") (pinfunction "1_1") (pintype "passive"))
    )
    (net (code "44") (name "Net-(R1003-Pad2)") (class "Default")
      (node (ref "R1003") (pin "2") (pinfunction "2_2") (pintype "passive"))
      (node (ref "R1004") (pin "1") (pinfunction "1_1") (pintype "passive"))
      (node (ref "R1005") (pin "1") (pinfunction "1_1") (pintype "passive"))
    )
    (net (code "45") (name "Net-(R1005-Pad2)") (class "Default")
      (node (ref "R1005") (pin "2") (pinfunction "2_2") (pintype "passive"))
      (node (ref "R1006") (pin "1") (pinfunction "1_1") (pintype "passive"))
      (node (ref "R1007") (pin "1") (pinfunction "1_1") (pintype "passive"))
    )
    (net (code "46") (name "Net-(U1001-0)") (class "Default")
      (node (ref "R1009") (pin "1") (pinfunction "1_1") (pintype "passive"))
      (node (ref "U1001") (pin "10") (pinfunction "0_10") (pintype "input"))
    )
    (net (code "47") (name "unconnected-(IC1001-NC-Pad11)") (class "Default")
      (node (ref "IC1001") (pin "11") (pinfunction "NC_11") (pintype "no_connect"))
    )
    (net (code "48") (name "unconnected-(J1001-Pad12)") (class "Default")
      (node (ref "J1001") (pin "12") (pinfunction "12_12") (pintype "passive"))
    )
    (net (code "49") (name "unconnected-(S1001-NO_1-Pad3)") (class "Default")
      (node (ref "S1001") (pin "3") (pinfunction "NO_1_3") (pintype "bidirectional"))
    )
    (net (code "50") (name "unconnected-(S1002-NO_1-Pad3)") (class "Default")
      (node (ref "S1002") (pin "3") (pinfunction "NO_1_3") (pintype "bidirectional"))
    )
    (net (code "51") (name "unconnected-(S1003-NO_1-Pad3)") (class "Default")
      (node (ref "S1003") (pin "3") (pinfunction "NO_1_3") (pintype "bidirectional"))
    )
    (net (code "52") (name "unconnected-(S1004-NO_1-Pad3)") (class "Default")
      (node (ref "S1004") (pin "3") (pinfunction "NO_1_3") (pintype "bidirectional"))
    )
    (net (code "53") (name "unconnected-(S1005-NO_1-Pad3)") (class "Default")
      (node (ref "S1005") (pin "3") (pinfunction "NO_1_3") (pintype "bidirectional"))
    )
    (net (code "54") (name "unconnected-(S1006-NO_1-Pad3)") (class "Default")
      (node (ref "S1006") (pin "3") (pinfunction "NO_1_3") (pintype "bidirectional"))
    )
    (net (code "55") (name "unconnected-(S1007-NO_1-Pad3)") (class "Default")
      (node (ref "S1007") (pin "3") (pinfunction "NO_1_3") (pintype "bidirectional"))
    )
    (net (code "56") (name "unconnected-(S1008-NO_1-Pad3)") (class "Default")
      (node (ref "S1008") (pin "3") (pinfunction "NO_1_3") (pintype "bidirectional"))
    )
    (net (code "57") (name "unconnected-(S1009-NO_1-Pad3)") (class "Default")
      (node (ref "S1009") (pin "3") (pinfunction "NO_1_3") (pintype "bidirectional"))
    )
    (net (code "58") (name "unconnected-(S1010-NO_1-Pad3)") (class "Default")
      (node (ref "S1010") (pin "3") (pinfunction "NO_1_3") (pintype "bidirectional"))
    )
    (net (code "59") (name "unconnected-(S1011-NO_1-Pad3)") (class "Default")
      (node (ref "S1011") (pin "3") (pinfunction "NO_1_3") (pintype "bidirectional"))
    )
    (net (code "60") (name "unconnected-(S1012-NO_1-Pad3)") (class "Default")
      (node (ref "S1012") (pin "3") (pinfunction "NO_1_3") (pintype "bidirectional"))
    )
    (net (code "61") (name "unconnected-(S1013-NO_1-Pad3)") (class "Default")
      (node (ref "S1013") (pin "3") (pinfunction "NO_1_3") (pintype "bidirectional"))
    )
    (net (code "62") (name "unconnected-(S1014-NO_1-Pad3)") (class "Default")
      (node (ref "S1014") (pin "3") (pinfunction "NO_1_3") (pintype "bidirectional"))
    )
    (net (code "63") (name "unconnected-(S1015-NO_1-Pad3)") (class "Default")
      (node (ref "S1015") (pin "3") (pinfunction "NO_1_3") (pintype "bidirectional"))
    )
    (net (code "64") (name "unconnected-(U1001-EO-Pad15)") (class "Default")
      (node (ref "U1001") (pin "15") (pinfunction "EO_15") (pintype "output"))
    )
    (net (code "65") (name "unconnected-(U1001-GS-Pad14)") (class "Default")
      (node (ref "U1001") (pin "14") (pinfunction "GS_14") (pintype "output"))
    )
    (net (code "66") (name "unconnected-(U1002-4A-Pad12)") (class "Default")
      (node (ref "U1002") (pin "12") (pinfunction "4A_12") (pintype "input"))
    )
    (net (code "67") (name "unconnected-(U1002-4B-Pad13)") (class "Default")
      (node (ref "U1002") (pin "13") (pinfunction "4B_13") (pintype "input"))
    )
    (net (code "68") (name "unconnected-(U1002-4Y-Pad11)") (class "Default")
      (node (ref "U1002") (pin "11") (pinfunction "4Y_11") (pintype "output"))
    )
    (net (code "69") (name "unconnected-(U1003-GS-Pad14)") (class "Default")
      (node (ref "U1003") (pin "14") (pinfunction "GS_14") (pintype "output"))
    )
    (net (code "70") (name "unconnected-(U1004-Pad1)") (class "Default")
      (node (ref "U1004") (pin "1") (pinfunction "1_1") (pintype "passive"))
    )
    (net (code "71") (name "unconnected-(U1004-Pad4)") (class "Default")
      (node (ref "U1004") (pin "4") (pinfunction "4_4") (pintype "passive"))
    )
  )
)
